# Alarm_clock_Schemetic.net
KiCad netlist of a schematic drawn in Altium Designer
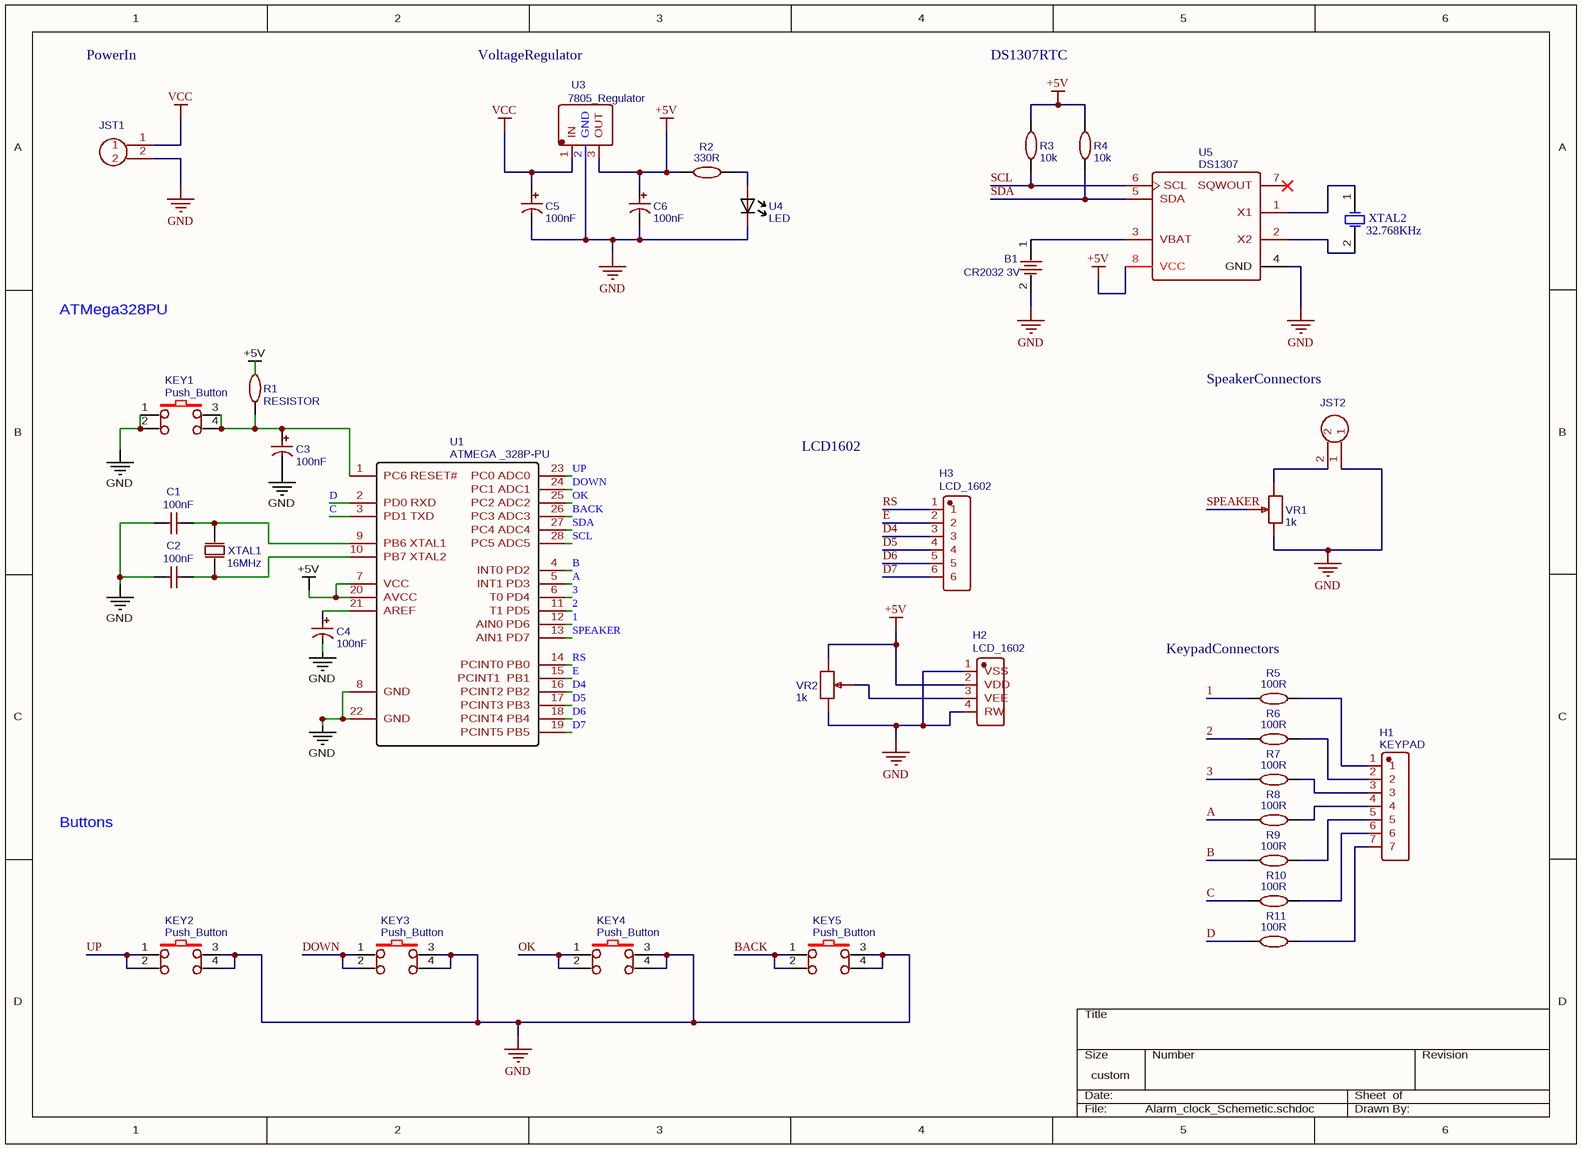
[diagram p0: Alarm_clock_Schemetic.schdoc]

(export (version "E")
  (design (tool "Eeschema 10.0.6"))
  (components
    (comp (ref "B1")
      (value "CR2032 3V")
      (footprint "BAT-TH_BS-2-1")
      (fields (field (name "BOM_MANUFACTURER PART") "BS-2-1") (field (name "BOM_SUPPLIER PART") "C70376"))
      (libsource (lib "altium-import") (part "root_3_CR2032 3V_"))
    )
    (comp (ref "C1")
      (value "100nF")
      (footprint "RAD-0.2")
      (fields
        (field (name "BOM_MANUFACTURER PART") "0.1UF(104) +-20% 63v")
        (field (name "BOM_SUPPLIER PART") "C19355")
      )
      (libsource (lib "") (part "root_0_100nF__1"))
    )
    (comp (ref "C2")
      (value "100nF")
      (footprint "RAD-0.2")
      (fields
        (field (name "BOM_MANUFACTURER PART") "0.1UF(104) +-20% 63v")
        (field (name "BOM_SUPPLIER PART") "C19355")
      )
      (libsource (lib "") (part "root_0_100nF__1"))
    )
    (comp (ref "C3")
      (value "100nF")
      (footprint "CAP-TH_BD5.0-P2.00-D0.8-FD")
      (fields (field (name "BOM_MANUFACTURER PART") "0.1UF 50V") (field (name "BOM_SUPPLIER PART") "C28061"))
      (libsource (lib "altium-import") (part "root_0_100nF_"))
    )
    (comp (ref "C4")
      (value "100nF")
      (footprint "CAP-TH_BD5.0-P2.00-D0.8-FD")
      (fields (field (name "BOM_MANUFACTURER PART") "0.1UF 50V") (field (name "BOM_SUPPLIER PART") "C28061"))
      (libsource (lib "altium-import") (part "root_0_100nF_"))
    )
    (comp (ref "C5")
      (value "100nF")
      (footprint "CAP-TH_BD5.0-P2.00-D0.8-FD")
      (fields (field (name "BOM_MANUFACTURER PART") "0.1UF 50V") (field (name "BOM_SUPPLIER PART") "C28061"))
      (libsource (lib "altium-import") (part "root_0_100nF_"))
    )
    (comp (ref "C6")
      (value "100nF")
      (footprint "CAP-TH_BD5.0-P2.00-D0.8-FD")
      (fields (field (name "BOM_MANUFACTURER PART") "0.1UF 50V") (field (name "BOM_SUPPLIER PART") "C28061"))
      (libsource (lib "altium-import") (part "root_0_100nF_"))
    )
    (comp (ref "H1")
      (value "KEYPAD")
      (footprint "HDR-TH_7P-P1.27-V-M")
      (fields
        (field (name "BOM_SUPPLIER PART") "C2832274")
        (field (name "BOM_MANUFACTURER PART") "PZ127V-11-07-H25")
        (field (name "CONTRIBUTOR") "LCSC")
      )
      (libsource (lib "altium-import") (part "root_0_KEYPAD_"))
    )
    (comp (ref "H2")
      (value "LCD_1602")
      (footprint "HDR-TH_4P-P2.00-V-M")
      (fields
        (field (name "BOM_SUPPLIER PART") "C2839989")
        (field (name "BOM_MANUFACTURER PART") "MH200V-11-04-1000")
        (field (name "CONTRIBUTOR") "LCSC")
      )
      (libsource (lib "altium-import") (part "root_0_LCD_1602_"))
    )
    (comp (ref "H3")
      (value "LCD_1602")
      (footprint "HDR-TH_6P-P2.54-H-F-W5.7")
      (fields
        (field (name "BOM_SUPPLIER PART") "C2833720")
        (field (name "BOM_MANUFACTURER PART") "FFH25402-S06B1001K6K")
        (field (name "CONTRIBUTOR") "LCSC")
      )
      (libsource (lib "") (part "root_0_LCD_1602__1"))
    )
    (comp (ref "JST1")
      (value "JST_2 PIN")
      (footprint "CONN-TH_XHB-2A")
      (fields
        (field (name "BOM_MANUFACTURER PART") "XHB-2A Connector")
        (field (name "BOM_SUPPLIER PART") "C57981")
      )
      (libsource (lib "altium-import") (part "root_0_JST_2 PIN_"))
    )
    (comp (ref "JST2")
      (value "JST_2 PIN")
      (footprint "CONN-TH_XHB-2A")
      (fields
        (field (name "BOM_MANUFACTURER PART") "XHB-2A Connector")
        (field (name "BOM_SUPPLIER PART") "C57981")
      )
      (libsource (lib "altium-import") (part "root_3_JST_2 PIN_"))
    )
    (comp (ref "KEY1")
      (value "Push_Button")
      (footprint "KEY-TH_4P-L6.0-W6.0-P4.50")
      (fields
        (field (name "BOM_SUPPLIER PART") "C59980")
        (field (name "BOM_MANUFACTURER PART") "button6*6*8.5")
      )
      (libsource (lib "altium-import") (part "root_0_Push_Button_"))
    )
    (comp (ref "KEY2")
      (value "Push_Button")
      (footprint "KEY-TH_4P-L6.0-W6.0-P4.50")
      (fields
        (field (name "BOM_SUPPLIER PART") "C59980")
        (field (name "BOM_MANUFACTURER PART") "button6*6*8.5")
      )
      (libsource (lib "altium-import") (part "root_0_Push_Button_"))
    )
    (comp (ref "KEY3")
      (value "Push_Button")
      (footprint "KEY-TH_4P-L6.0-W6.0-P4.50")
      (fields
        (field (name "BOM_SUPPLIER PART") "C59980")
        (field (name "BOM_MANUFACTURER PART") "button6*6*8.5")
      )
      (libsource (lib "altium-import") (part "root_0_Push_Button_"))
    )
    (comp (ref "KEY4")
      (value "Push_Button")
      (footprint "KEY-TH_4P-L6.0-W6.0-P4.50")
      (fields
        (field (name "BOM_SUPPLIER PART") "C59980")
        (field (name "BOM_MANUFACTURER PART") "button6*6*8.5")
      )
      (libsource (lib "altium-import") (part "root_0_Push_Button_"))
    )
    (comp (ref "KEY5")
      (value "Push_Button")
      (footprint "KEY-TH_4P-L6.0-W6.0-P4.50")
      (fields
        (field (name "BOM_SUPPLIER PART") "C59980")
        (field (name "BOM_MANUFACTURER PART") "button6*6*8.5")
      )
      (libsource (lib "altium-import") (part "root_0_Push_Button_"))
    )
    (comp (ref "R1")
      (value "RESISTOR")
      (footprint "AXIAL-0.4")
      (fields
        (field (name "POWER") "1/4W")
        (field (name "TOLERANCE") "±1%")
        (field (name "BOM_SUPPLIER PART") "E57439")
      )
      (libsource (lib "altium-import") (part "root_1_RESISTOR_"))
    )
    (comp (ref "R2")
      (value "330R")
      (footprint "AXIAL-0.4")
      (fields
        (field (name "POWER") "1/4W")
        (field (name "TOLERANCE") "±1%")
        (field (name "BOM_SUPPLIER PART") "E57439")
      )
      (libsource (lib "altium-import") (part "root_0_330R_"))
    )
    (comp (ref "R3")
      (value "10k")
      (footprint "AXIAL-0.4")
      (fields
        (field (name "POWER") "1/4W")
        (field (name "TOLERANCE") "±1%")
        (field (name "BOM_SUPPLIER PART") "E57439")
      )
      (libsource (lib "altium-import") (part "root_1_10k_"))
    )
    (comp (ref "R4")
      (value "10k")
      (footprint "AXIAL-0.4")
      (fields
        (field (name "POWER") "1/4W")
        (field (name "TOLERANCE") "±1%")
        (field (name "BOM_SUPPLIER PART") "E57439")
      )
      (libsource (lib "altium-import") (part "root_1_10k_"))
    )
    (comp (ref "R5")
      (value "100R")
      (footprint "AXIAL-0.4")
      (fields
        (field (name "POWER") "1/4W")
        (field (name "TOLERANCE") "±1%")
        (field (name "BOM_SUPPLIER PART") "E57439")
      )
      (libsource (lib "altium-import") (part "root_0_100R_"))
    )
    (comp (ref "R6")
      (value "100R")
      (footprint "AXIAL-0.4")
      (fields
        (field (name "POWER") "1/4W")
        (field (name "TOLERANCE") "±1%")
        (field (name "BOM_SUPPLIER PART") "E57439")
      )
      (libsource (lib "altium-import") (part "root_0_100R_"))
    )
    (comp (ref "R7")
      (value "100R")
      (footprint "AXIAL-0.4")
      (fields
        (field (name "POWER") "1/4W")
        (field (name "TOLERANCE") "±1%")
        (field (name "BOM_SUPPLIER PART") "E57439")
      )
      (libsource (lib "altium-import") (part "root_0_100R_"))
    )
    (comp (ref "R8")
      (value "100R")
      (footprint "AXIAL-0.4")
      (fields
        (field (name "POWER") "1/4W")
        (field (name "TOLERANCE") "±1%")
        (field (name "BOM_SUPPLIER PART") "E57439")
      )
      (libsource (lib "altium-import") (part "root_0_100R_"))
    )
    (comp (ref "R9")
      (value "100R")
      (footprint "AXIAL-0.4")
      (fields
        (field (name "POWER") "1/4W")
        (field (name "TOLERANCE") "±1%")
        (field (name "BOM_SUPPLIER PART") "E57439")
      )
      (libsource (lib "altium-import") (part "root_0_100R_"))
    )
    (comp (ref "R10")
      (value "100R")
      (footprint "AXIAL-0.4")
      (fields
        (field (name "POWER") "1/4W")
        (field (name "TOLERANCE") "±1%")
        (field (name "BOM_SUPPLIER PART") "E57439")
      )
      (libsource (lib "altium-import") (part "root_0_100R_"))
    )
    (comp (ref "R11")
      (value "100R")
      (footprint "AXIAL-0.4")
      (fields
        (field (name "POWER") "1/4W")
        (field (name "TOLERANCE") "±1%")
        (field (name "BOM_SUPPLIER PART") "E57439")
      )
      (libsource (lib "altium-import") (part "root_0_100R_"))
    )
    (comp (ref "U1")
      (value "ATMEGA _328P-PU")
      (footprint "DIP-28_L34.6-W7.3-P2.54-LS10.2-BL")
      (fields
        (field (name "BOM_MANUFACTURER PART") "ATMEGA328P-PU")
        (field (name "BOM_SUPPLIER PART") "C33901")
        (field (name "CONTRIBUTOR") "LCSC")
      )
      (libsource (lib "altium-import") (part "root_0_ATMEGA _328P-PU_"))
    )
    (comp (ref "U3")
      (value "7805_Regulator")
      (footprint "TO-220-3_L10.0-W4.5-P2.54-L")
      (fields
        (field (name "BOM_SUPPLIER PART") "C305416")
        (field (name "BOM_MANUFACTURER PART") "7805")
        (field (name "CONTRIBUTOR") "LCSC")
      )
      (libsource (lib "altium-import") (part "root_1_7805_Regulator_"))
    )
    (comp (ref "U4")
      (value "LED")
      (footprint "5MM LED")
      (fields (field (name "BOM_MANUFACTURER PART") "5mm LED") (field (name "CONTRIBUTOR") "Axbri"))
      (libsource (lib "altium-import") (part "root_3_LED_"))
    )
    (comp (ref "U5")
      (value "DS1307")
      (footprint "DIP-8_L9.8-W6.6-P2.54-LS7.6-BL")
      (fields (field (name "BOM_MANUFACTURER PART") "DS1307+") (field (name "BOM_SUPPLIER PART") "C59267"))
      (libsource (lib "altium-import") (part "root_0_DS1307_"))
    )
    (comp (ref "VR1")
      (value "1k")
      (footprint "RES-ADJ-TH_3296W")
      (fields (field (name "BOM_MANUFACTURER PART") "Pot-100R") (field (name "BOM_SUPPLIER PART") "C13649"))
      (libsource (lib "altium-import") (part "root_0_1k_"))
    )
    (comp (ref "VR2")
      (value "1k")
      (footprint "RES-ADJ-TH_3296W")
      (fields (field (name "BOM_MANUFACTURER PART") "Pot-100R") (field (name "BOM_SUPPLIER PART") "C13649"))
      (libsource (lib "altium-import") (part "root_2_1k_"))
    )
    (comp (ref "XTAL1")
      (value "16MHz")
      (footprint "16MHZ_OSC [PCB]")
      (fields
        (field (name "BOM_MANUFACTURER PART") "0SC-16MHz")
        (field (name "CONTRIBUTOR") "Mantas Petrauskas")
      )
      (libsource (lib "altium-import") (part "root_1_16MHz_"))
    )
    (comp (ref "XTAL2")
      (value "32.768KHz")
      (footprint "R38")
      (description "Crystal Oscillator")
      (fields (field (name "PUBLISHER") "Altium Limited"))
      (libsource (lib "Miscellaneous Devices") (part "XTAL"))
    )
  )
  (nets
    (net (code "1") (name "+5V") (class "Default")
      (node (ref "C6") (pin "1") (pinfunction "1_1") (pintype "passive"))
      (node (ref "H2") (pin "2") (pinfunction "VDD_2") (pintype "passive"))
      (node (ref "R1") (pin "2") (pinfunction "2_2") (pintype "passive"))
      (node (ref "R2") (pin "1") (pinfunction "1_1") (pintype "passive"))
      (node (ref "R3") (pin "2") (pinfunction "2_2") (pintype "passive"))
      (node (ref "R4") (pin "2") (pinfunction "2_2") (pintype "passive"))
      (node (ref "U1") (pin "20") (pinfunction "AVCC_20") (pintype "passive"))
      (node (ref "U1") (pin "7") (pinfunction "VCC_7") (pintype "passive"))
      (node (ref "U3") (pin "3") (pinfunction "OUT_3") (pintype "passive"))
      (node (ref "U5") (pin "8") (pinfunction "VCC_8") (pintype "passive"))
      (node (ref "VR2") (pin "3") (pinfunction "3_3") (pintype "passive"))
    )
    (net (code "2") (name "/1") (class "Default")
      (node (ref "R5") (pin "1") (pinfunction "1_1") (pintype "passive"))
      (node (ref "U1") (pin "12") (pinfunction "AIN0_PD6_12") (pintype "passive"))
    )
    (net (code "3") (name "/2") (class "Default")
      (node (ref "R6") (pin "1") (pinfunction "1_1") (pintype "passive"))
      (node (ref "U1") (pin "11") (pinfunction "T1_PD5_11") (pintype "passive"))
    )
    (net (code "4") (name "/3") (class "Default")
      (node (ref "R7") (pin "1") (pinfunction "1_1") (pintype "passive"))
      (node (ref "U1") (pin "6") (pinfunction "T0_PD4_6") (pintype "passive"))
    )
    (net (code "5") (name "/A") (class "Default")
      (node (ref "R8") (pin "1") (pinfunction "1_1") (pintype "passive"))
      (node (ref "U1") (pin "5") (pinfunction "INT1_PD3_5") (pintype "passive"))
    )
    (net (code "6") (name "/B") (class "Default")
      (node (ref "R9") (pin "1") (pinfunction "1_1") (pintype "passive"))
      (node (ref "U1") (pin "4") (pinfunction "INT0_PD2_4") (pintype "passive"))
    )
    (net (code "7") (name "/BACK") (class "Default")
      (node (ref "KEY5") (pin "1") (pinfunction "1_1") (pintype "passive"))
      (node (ref "KEY5") (pin "2") (pinfunction "2_2") (pintype "passive"))
      (node (ref "U1") (pin "26") (pinfunction "PC3_ADC3_26") (pintype "passive"))
    )
    (net (code "8") (name "/C") (class "Default")
      (node (ref "R10") (pin "1") (pinfunction "1_1") (pintype "passive"))
      (node (ref "U1") (pin "3") (pinfunction "PD1_TXD_3") (pintype "passive"))
    )
    (net (code "9") (name "/D") (class "Default")
      (node (ref "R11") (pin "1") (pinfunction "1_1") (pintype "passive"))
      (node (ref "U1") (pin "2") (pinfunction "PD0_RXD_2") (pintype "passive"))
    )
    (net (code "10") (name "/D4") (class "Default")
      (node (ref "H3") (pin "3") (pinfunction "3_3") (pintype "passive"))
      (node (ref "U1") (pin "16") (pinfunction "PCINT2_PB2_16") (pintype "passive"))
    )
    (net (code "11") (name "/D5") (class "Default")
      (node (ref "H3") (pin "4") (pinfunction "4_4") (pintype "passive"))
      (node (ref "U1") (pin "17") (pinfunction "PCINT3_PB3_17") (pintype "passive"))
    )
    (net (code "12") (name "/D6") (class "Default")
      (node (ref "H3") (pin "5") (pinfunction "5_5") (pintype "passive"))
      (node (ref "U1") (pin "18") (pinfunction "PCINT4_PB4_18") (pintype "passive"))
    )
    (net (code "13") (name "/D7") (class "Default")
      (node (ref "H3") (pin "6") (pinfunction "6_6") (pintype "passive"))
      (node (ref "U1") (pin "19") (pinfunction "PCINT5_PB5_19") (pintype "passive"))
    )
    (net (code "14") (name "/DOWN") (class "Default")
      (node (ref "KEY3") (pin "1") (pinfunction "1_1") (pintype "passive"))
      (node (ref "KEY3") (pin "2") (pinfunction "2_2") (pintype "passive"))
      (node (ref "U1") (pin "24") (pinfunction "PC1_ADC1_24") (pintype "passive"))
    )
    (net (code "15") (name "/E") (class "Default")
      (node (ref "H3") (pin "2") (pinfunction "2_2") (pintype "passive"))
      (node (ref "U1") (pin "15") (pinfunction "PCINT1__PB1_15") (pintype "passive"))
    )
    (net (code "16") (name "/OK") (class "Default")
      (node (ref "KEY4") (pin "1") (pinfunction "1_1") (pintype "passive"))
      (node (ref "KEY4") (pin "2") (pinfunction "2_2") (pintype "passive"))
      (node (ref "U1") (pin "25") (pinfunction "PC2_ADC2_25") (pintype "passive"))
    )
    (net (code "17") (name "/RS") (class "Default")
      (node (ref "H3") (pin "1") (pinfunction "1_1") (pintype "passive"))
      (node (ref "U1") (pin "14") (pinfunction "PCINT0_PB0_14") (pintype "passive"))
    )
    (net (code "18") (name "/SCL") (class "Default")
      (node (ref "R3") (pin "1") (pinfunction "1_1") (pintype "passive"))
      (node (ref "U1") (pin "28") (pinfunction "PC5_ADC5_28") (pintype "passive"))
      (node (ref "U5") (pin "6") (pinfunction "SCL_6") (pintype "passive"))
    )
    (net (code "19") (name "/SDA") (class "Default")
      (node (ref "R4") (pin "1") (pinfunction "1_1") (pintype "passive"))
      (node (ref "U1") (pin "27") (pinfunction "PC4_ADC4_27") (pintype "passive"))
      (node (ref "U5") (pin "5") (pinfunction "SDA_5") (pintype "passive"))
    )
    (net (code "20") (name "/SPEAKER") (class "Default")
      (node (ref "U1") (pin "13") (pinfunction "AIN1_PD7_13") (pintype "passive"))
      (node (ref "VR1") (pin "2") (pinfunction "2_2") (pintype "passive"))
    )
    (net (code "21") (name "/UP") (class "Default")
      (node (ref "KEY2") (pin "1") (pinfunction "1_1") (pintype "passive"))
      (node (ref "KEY2") (pin "2") (pinfunction "2_2") (pintype "passive"))
      (node (ref "U1") (pin "23") (pinfunction "PC0_ADC0_23") (pintype "passive"))
    )
    (net (code "22") (name "GND") (class "Default")
      (node (ref "B1") (pin "2") (pinfunction "2_2") (pintype "passive"))
      (node (ref "C1") (pin "1") (pinfunction "1_1") (pintype "passive"))
      (node (ref "C2") (pin "1") (pinfunction "1_1") (pintype "passive"))
      (node (ref "C3") (pin "2") (pinfunction "2_2") (pintype "passive"))
      (node (ref "C4") (pin "2") (pinfunction "2_2") (pintype "passive"))
      (node (ref "C5") (pin "2") (pinfunction "2_2") (pintype "passive"))
      (node (ref "C6") (pin "2") (pinfunction "2_2") (pintype "passive"))
      (node (ref "H2") (pin "1") (pinfunction "VSS_1") (pintype "passive"))
      (node (ref "H2") (pin "4") (pinfunction "RW_4") (pintype "passive"))
      (node (ref "JST1") (pin "2") (pinfunction "2_2") (pintype "passive"))
      (node (ref "JST2") (pin "1") (pinfunction "1_1") (pintype "passive"))
      (node (ref "KEY1") (pin "1") (pinfunction "1_1") (pintype "passive"))
      (node (ref "KEY1") (pin "2") (pinfunction "2_2") (pintype "passive"))
      (node (ref "KEY2") (pin "3") (pinfunction "3_3") (pintype "passive"))
      (node (ref "KEY2") (pin "4") (pinfunction "4_4") (pintype "passive"))
      (node (ref "KEY3") (pin "3") (pinfunction "3_3") (pintype "passive"))
      (node (ref "KEY3") (pin "4") (pinfunction "4_4") (pintype "passive"))
      (node (ref "KEY4") (pin "3") (pinfunction "3_3") (pintype "passive"))
      (node (ref "KEY4") (pin "4") (pinfunction "4_4") (pintype "passive"))
      (node (ref "KEY5") (pin "3") (pinfunction "3_3") (pintype "passive"))
      (node (ref "KEY5") (pin "4") (pinfunction "4_4") (pintype "passive"))
      (node (ref "U1") (pin "22") (pinfunction "GND_22") (pintype "passive"))
      (node (ref "U1") (pin "8") (pinfunction "GND_8") (pintype "passive"))
      (node (ref "U3") (pin "2") (pinfunction "GND_2") (pintype "passive"))
      (node (ref "U4") (pin "2") (pinfunction "2_2") (pintype "passive"))
      (node (ref "U5") (pin "4") (pinfunction "GND_4") (pintype "passive"))
      (node (ref "VR1") (pin "3") (pinfunction "3_3") (pintype "passive"))
      (node (ref "VR2") (pin "1") (pinfunction "1_1") (pintype "passive"))
    )
    (net (code "23") (name "Net-(H1-Pad1)") (class "Default")
      (node (ref "H1") (pin "1") (pinfunction "1_1") (pintype "passive"))
      (node (ref "R5") (pin "2") (pinfunction "2_2") (pintype "passive"))
    )
    (net (code "24") (name "Net-(H1-Pad2)") (class "Default")
      (node (ref "H1") (pin "2") (pinfunction "2_2") (pintype "passive"))
      (node (ref "R6") (pin "2") (pinfunction "2_2") (pintype "passive"))
    )
    (net (code "25") (name "Net-(H1-Pad3)") (class "Default")
      (node (ref "H1") (pin "3") (pinfunction "3_3") (pintype "passive"))
      (node (ref "R7") (pin "2") (pinfunction "2_2") (pintype "passive"))
    )
    (net (code "26") (name "Net-(H1-Pad4)") (class "Default")
      (node (ref "H1") (pin "4") (pinfunction "4_4") (pintype "passive"))
      (node (ref "R8") (pin "2") (pinfunction "2_2") (pintype "passive"))
    )
    (net (code "27") (name "Net-(H1-Pad5)") (class "Default")
      (node (ref "H1") (pin "5") (pinfunction "5_5") (pintype "passive"))
      (node (ref "R9") (pin "2") (pinfunction "2_2") (pintype "passive"))
    )
    (net (code "28") (name "Net-(H1-Pad6)") (class "Default")
      (node (ref "H1") (pin "6") (pinfunction "6_6") (pintype "passive"))
      (node (ref "R10") (pin "2") (pinfunction "2_2") (pintype "passive"))
    )
    (net (code "29") (name "Net-(H1-Pad7)") (class "Default")
      (node (ref "H1") (pin "7") (pinfunction "7_7") (pintype "passive"))
      (node (ref "R11") (pin "2") (pinfunction "2_2") (pintype "passive"))
    )
    (net (code "30") (name "Net-(H2-VEE)") (class "Default")
      (node (ref "H2") (pin "3") (pinfunction "VEE_3") (pintype "passive"))
      (node (ref "VR2") (pin "2") (pinfunction "2_2") (pintype "passive"))
    )
    (net (code "31") (name "Net-(JST2-Pad2)") (class "Default")
      (node (ref "JST2") (pin "2") (pinfunction "2_2") (pintype "passive"))
      (node (ref "VR1") (pin "1") (pinfunction "1_1") (pintype "passive"))
    )
    (net (code "32") (name "Net-(R2-Pad2)") (class "Default")
      (node (ref "R2") (pin "2") (pinfunction "2_2") (pintype "passive"))
      (node (ref "U4") (pin "1") (pinfunction "1_1") (pintype "passive"))
    )
    (net (code "33") (name "Net-(U1-AREF)") (class "Default")
      (node (ref "C4") (pin "1") (pinfunction "1_1") (pintype "passive"))
      (node (ref "U1") (pin "21") (pinfunction "AREF_21") (pintype "passive"))
    )
    (net (code "34") (name "Net-(U1-PB6_XTAL1)") (class "Default")
      (node (ref "C1") (pin "2") (pinfunction "2_2") (pintype "passive"))
      (node (ref "U1") (pin "9") (pinfunction "PB6_XTAL1_9") (pintype "passive"))
      (node (ref "XTAL1") (pin "1") (pinfunction "OSC1_1") (pintype "passive"))
    )
    (net (code "35") (name "Net-(U1-PB7_XTAL2)") (class "Default")
      (node (ref "C2") (pin "2") (pinfunction "2_2") (pintype "passive"))
      (node (ref "U1") (pin "10") (pinfunction "PB7_XTAL2_10") (pintype "passive"))
      (node (ref "XTAL1") (pin "2") (pinfunction "OSC2_2") (pintype "passive"))
    )
    (net (code "36") (name "Net-(U1-PC6_RESET#)") (class "Default")
      (node (ref "C3") (pin "1") (pinfunction "1_1") (pintype "passive"))
      (node (ref "KEY1") (pin "3") (pinfunction "3_3") (pintype "passive"))
      (node (ref "KEY1") (pin "4") (pinfunction "4_4") (pintype "passive"))
      (node (ref "R1") (pin "1") (pinfunction "1_1") (pintype "passive"))
      (node (ref "U1") (pin "1") (pinfunction "PC6_RESET#_1") (pintype "passive"))
    )
    (net (code "37") (name "Net-(U5-VBAT)") (class "Default")
      (node (ref "B1") (pin "1") (pinfunction "1_1") (pintype "passive"))
      (node (ref "U5") (pin "3") (pinfunction "VBAT_3") (pintype "passive"))
    )
    (net (code "38") (name "Net-(U5-X1)") (class "Default")
      (node (ref "U5") (pin "1") (pinfunction "X1_1") (pintype "passive"))
      (node (ref "XTAL2") (pin "1") (pinfunction "OSC1_1") (pintype "passive"))
    )
    (net (code "39") (name "Net-(U5-X2)") (class "Default")
      (node (ref "U5") (pin "2") (pinfunction "X2_2") (pintype "passive"))
      (node (ref "XTAL2") (pin "2") (pinfunction "OSC2_2") (pintype "passive"))
    )
    (net (code "40") (name "VCC") (class "Default")
      (node (ref "C5") (pin "1") (pinfunction "1_1") (pintype "passive"))
      (node (ref "JST1") (pin "1") (pinfunction "1_1") (pintype "passive"))
      (node (ref "U3") (pin "1") (pinfunction "IN_1") (pintype "passive"))
    )
    (net (code "41") (name "unconnected-(U5-SQWOUT-Pad7)") (class "Default")
      (node (ref "U5") (pin "7") (pinfunction "SQWOUT_7") (pintype "passive+no_connect"))
    )
  )
)
